# cjc.net
KiCad netlist of a schematic drawn in Altium Designer
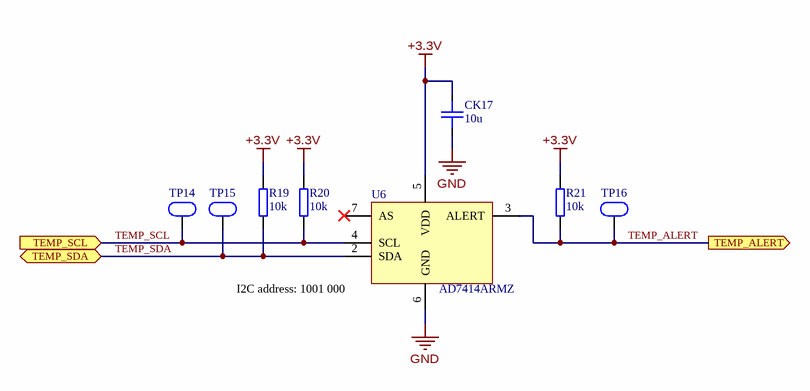
[diagram p0: cjc.SchDoc]

(export (version "E")
  (design (tool "Eeschema 10.0.6"))
  (components
    (comp (ref "CK17")
      (value "10u")
      (footprint "CAPC3225X27N(SMC1210)")
      (description "C; 10u; 50V; 10%; X7R; ??;")
      (fields
        (field (name "MANUFACTURER") "Murata: GRM32ER71H106KA12L;;Samsung Electro-mechanics: CL32B106KBJNNNE")
      )
      (libsource (lib "altium_sql") (part "CK"))
    )
    (comp (ref "R19")
      (value "10k")
      (footprint "RESC2012X06N(SMR0805)")
      (description "R; 10k; 0.125W; 1%; 150V; Thick Film; ±100ppm/K; 1x;")
      (libsource (lib "altium_sql") (part "R"))
    )
    (comp (ref "R20")
      (value "10k")
      (footprint "RESC2012X06N(SMR0805)")
      (description "R; 10k; 0.125W; 1%; 150V; Thick Film; ±100ppm/K; 1x;")
      (libsource (lib "altium_sql") (part "R"))
    )
    (comp (ref "R21")
      (value "10k")
      (footprint "RESC2012X06N(SMR0805)")
      (description "R; 10k; 0.125W; 1%; 150V; Thick Film; ±100ppm/K; 1x;")
      (libsource (lib "altium_sql") (part "R"))
    )
    (comp (ref "TP14")
      (value "Test Point")
      (footprint "SMD_Testpoint_Onelayer")
      (description "Con; Test Point; 1x; PCB; ??; ??V; ??A; ??; Tin; Contact;")
      (fields (field (name "MANUFACTURER") "Harwin: S1751-46R") (field (name "CONNECTOR_PART") "Contact"))
      (libsource (lib "altium_sql") (part "EJ+TESTPOINTXX0"))
    )
    (comp (ref "TP15")
      (value "Test Point")
      (footprint "SMD_Testpoint_Onelayer")
      (description "Con; Test Point; 1x; PCB; ??; ??V; ??A; ??; Tin; Contact;")
      (fields (field (name "MANUFACTURER") "Harwin: S1751-46R") (field (name "CONNECTOR_PART") "Contact"))
      (libsource (lib "altium_sql") (part "EJ+TESTPOINTXX0"))
    )
    (comp (ref "TP16")
      (value "Test Point")
      (footprint "SMD_Testpoint_Onelayer")
      (description "Con; Test Point; 1x; PCB; ??; ??V; ??A; ??; Tin; Contact;")
      (fields (field (name "MANUFACTURER") "Harwin: S1751-46R") (field (name "CONNECTOR_PART") "Contact"))
      (libsource (lib "altium_sql") (part "EJ+TESTPOINTXX0"))
    )
    (comp (ref "U6")
      (value "AD7414ARMZ")
      (footprint "RM_8(MSOP-8)")
      (description "Sen; Temperature [°C]; Digital/PWM; 0.5%;")
      (fields (field (name "MANUFACTURER") "ANALOG DEVICES: AD7414ARMZ-0;;ANALOG DEVICES: AD7414ARMZ-0REEL7"))
      (libsource (lib "altium_sql") (part "EU+AD7414ARMZXX0"))
    )
  )
  (nets
    (net (code "1") (name "+3.3V") (class "Default")
      (node (ref "CK17") (pin "1") (pinfunction "1_1") (pintype "passive"))
      (node (ref "R19") (pin "2") (pinfunction "2_2") (pintype "passive"))
      (node (ref "R20") (pin "2") (pinfunction "2_2") (pintype "passive"))
      (node (ref "R21") (pin "2") (pinfunction "2_2") (pintype "passive"))
      (node (ref "U6") (pin "5") (pinfunction "VDD_5") (pintype "power_in"))
    )
    (net (code "2") (name "/TEMP_ALERT") (class "Default")
      (node (ref "R21") (pin "1") (pinfunction "1_1") (pintype "passive"))
      (node (ref "TP16") (pin "1") (pintype "passive"))
      (node (ref "U6") (pin "3") (pinfunction "ALERT_3") (pintype "passive"))
    )
    (net (code "3") (name "/TEMP_SCL") (class "Default")
      (node (ref "R20") (pin "1") (pinfunction "1_1") (pintype "passive"))
      (node (ref "TP14") (pin "1") (pintype "passive"))
      (node (ref "U6") (pin "4") (pinfunction "SCL_4") (pintype "passive"))
    )
    (net (code "4") (name "/TEMP_SDA") (class "Default")
      (node (ref "R19") (pin "1") (pinfunction "1_1") (pintype "passive"))
      (node (ref "TP15") (pin "1") (pintype "passive"))
      (node (ref "U6") (pin "2") (pinfunction "SDA_2") (pintype "passive"))
    )
    (net (code "5") (name "GND") (class "Default")
      (node (ref "CK17") (pin "2") (pinfunction "2_2") (pintype "passive"))
      (node (ref "U6") (pin "6") (pinfunction "GND_6") (pintype "passive"))
    )
    (net (code "6") (name "unconnected-(U6-AS-Pad7)") (class "Default")
      (node (ref "U6") (pin "7") (pinfunction "AS_7") (pintype "passive+no_connect"))
    )
  )
)
